# SCH.net
KiCad netlist of a schematic drawn in EasyEDA Pro
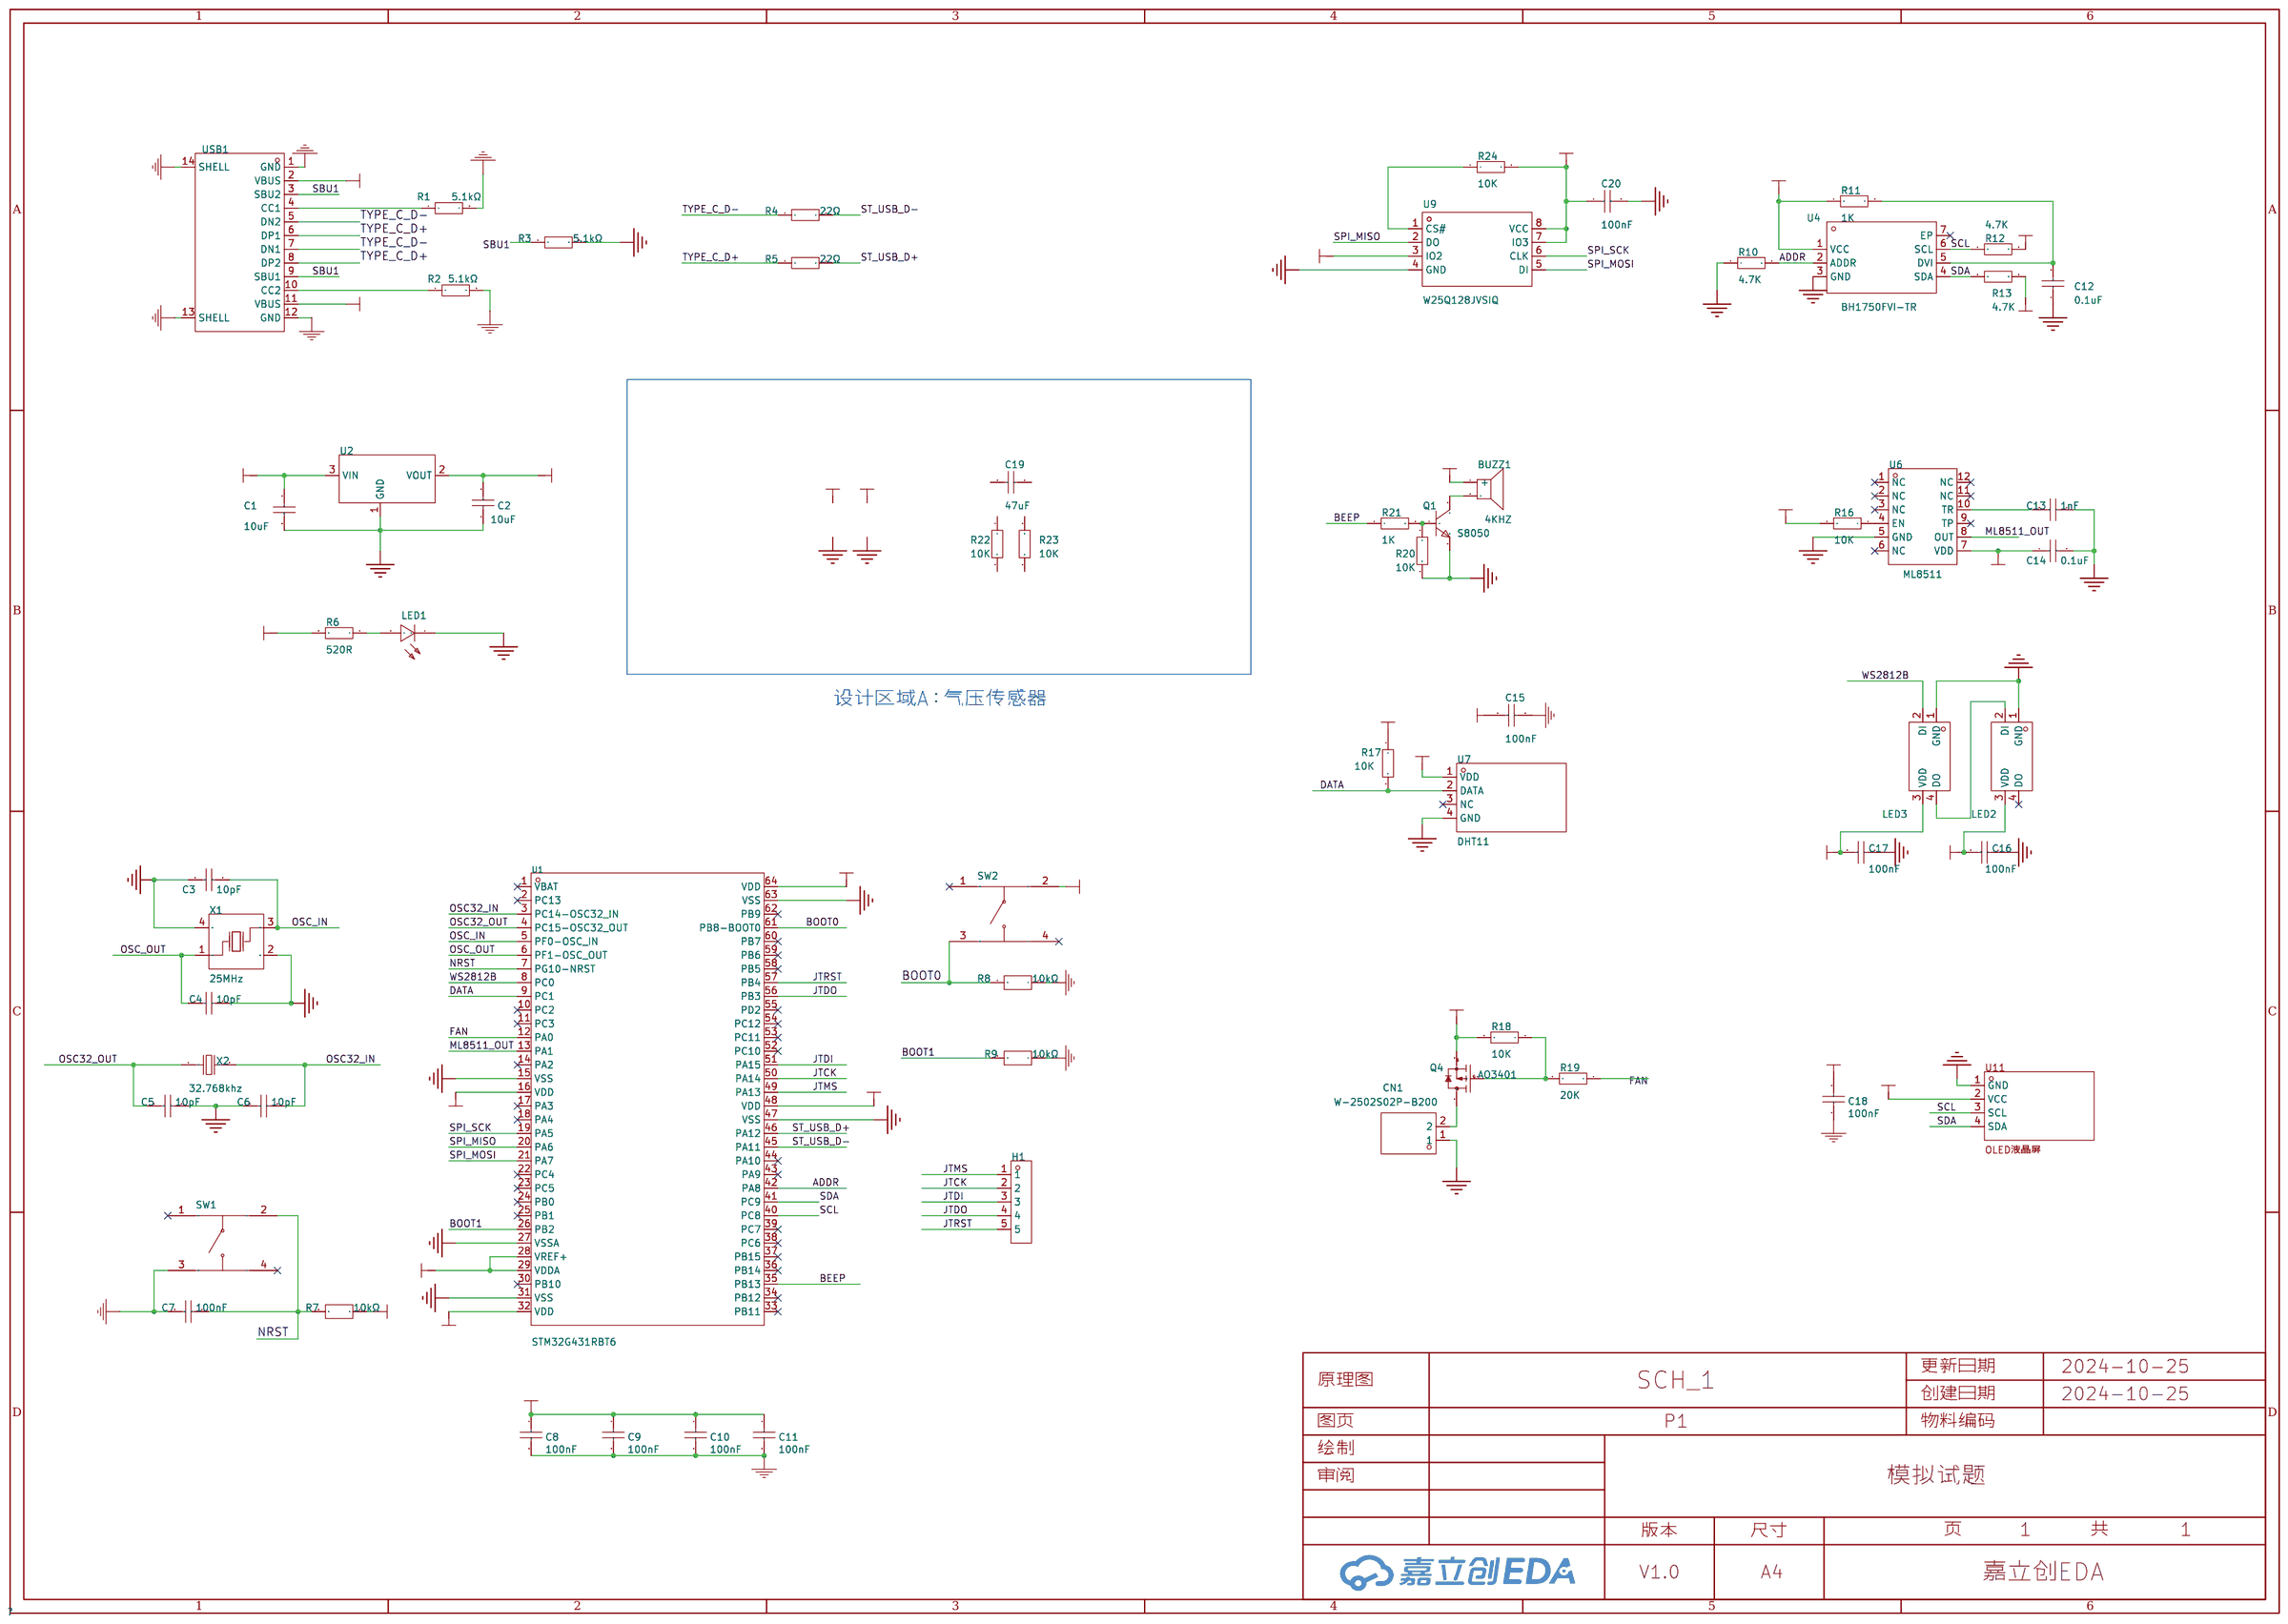
[diagram p0: schematic sheet]

(export (version "E")
  (design (tool "Eeschema 10.0.6"))
  (components
    (comp (ref "BUZZ1")
      (value "4KHZ")
      (footprint "easyedapro:BUZ-TH_BD12.0-P7.60-D0.6-FD")
      (description "驱动方式:有源(内含驱动线路);构造类型:电磁式;频率:2.7kHz;声压(SPL):85dB;")
      (fields (field (name "Manufacturer Part") "TMB12A05") (field (name "Manufacturer") "华能"))
      (libsource (lib "easyedapro") (part "TMB12A05"))
    )
    (comp (ref "C1")
      (value "10uF")
      (footprint "easyedapro:C0805")
      (description "容值:100nF;精度:±10%;额定电压:50V;材质(温度系数):X7R;")
      (fields
        (field (name "Manufacturer Part") "CC0805KRX7R9BB104")
        (field (name "Manufacturer") "YAGEO(国巨)")
      )
      (libsource (lib "easyedapro") (part "CC0805KRX7R9BB104"))
    )
    (comp (ref "C2")
      (value "10uF")
      (footprint "easyedapro:C0805")
      (description "容值:100nF;精度:±10%;额定电压:50V;材质(温度系数):X7R;")
      (fields
        (field (name "Manufacturer Part") "CC0805KRX7R9BB104")
        (field (name "Manufacturer") "YAGEO(国巨)")
      )
      (libsource (lib "easyedapro") (part "CC0805KRX7R9BB104"))
    )
    (comp (ref "C3")
      (value "10pF")
      (footprint "easyedapro:C0805")
      (description "容值:100nF;精度:±10%;额定电压:50V;材质(温度系数):X7R;")
      (fields
        (field (name "Manufacturer Part") "CC0805KRX7R9BB104")
        (field (name "Manufacturer") "YAGEO(国巨)")
      )
      (libsource (lib "easyedapro") (part "CC0805KRX7R9BB104"))
    )
    (comp (ref "C4")
      (value "10pF")
      (footprint "easyedapro:C0805")
      (description "容值:100nF;精度:±10%;额定电压:50V;材质(温度系数):X7R;")
      (fields
        (field (name "Manufacturer Part") "CC0805KRX7R9BB104")
        (field (name "Manufacturer") "YAGEO(国巨)")
      )
      (libsource (lib "easyedapro") (part "CC0805KRX7R9BB104"))
    )
    (comp (ref "C5")
      (value "10pF")
      (footprint "easyedapro:C0805")
      (description "容值:100nF;精度:±10%;额定电压:50V;材质(温度系数):X7R;")
      (fields
        (field (name "Manufacturer Part") "CC0805KRX7R9BB104")
        (field (name "Manufacturer") "YAGEO(国巨)")
      )
      (libsource (lib "easyedapro") (part "CC0805KRX7R9BB104"))
    )
    (comp (ref "C6")
      (value "10pF")
      (footprint "easyedapro:C0805")
      (description "容值:100nF;精度:±10%;额定电压:50V;材质(温度系数):X7R;")
      (fields
        (field (name "Manufacturer Part") "CC0805KRX7R9BB104")
        (field (name "Manufacturer") "YAGEO(国巨)")
      )
      (libsource (lib "easyedapro") (part "CC0805KRX7R9BB104"))
    )
    (comp (ref "C7") (value "100nF") (libsource (lib "easyedapro") (part "100nf")))
    (comp (ref "C8") (value "100nF") (libsource (lib "easyedapro") (part "100nf")))
    (comp (ref "C9") (value "100nF") (libsource (lib "easyedapro") (part "100nf")))
    (comp (ref "C10") (value "100nF") (libsource (lib "easyedapro") (part "100nf")))
    (comp (ref "C11") (value "100nF") (libsource (lib "easyedapro") (part "100nf")))
    (comp (ref "C12")
      (value "0.1uF")
      (footprint "easyedapro:C0805")
      (description "容值:100nF;精度:±10%;额定电压:50V;材质(温度系数):X7R;")
      (fields
        (field (name "Manufacturer Part") "CC0805KRX7R9BB104")
        (field (name "Manufacturer") "YAGEO(国巨)")
      )
      (libsource (lib "easyedapro") (part "CC0805KRX7R9BB104"))
    )
    (comp (ref "C13")
      (value "1nF")
      (footprint "easyedapro:C0805")
      (description "容值:100nF;精度:±10%;额定电压:50V;材质(温度系数):X7R;")
      (fields
        (field (name "Manufacturer Part") "CC0805KRX7R9BB104")
        (field (name "Manufacturer") "YAGEO(国巨)")
      )
      (libsource (lib "easyedapro") (part "CC0805KRX7R9BB104"))
    )
    (comp (ref "C14")
      (value "0.1uF")
      (footprint "easyedapro:C0805")
      (description "容值:100nF;精度:±10%;额定电压:50V;材质(温度系数):X7R;")
      (fields
        (field (name "Manufacturer Part") "CC0805KRX7R9BB104")
        (field (name "Manufacturer") "YAGEO(国巨)")
      )
      (libsource (lib "easyedapro") (part "CC0805KRX7R9BB104"))
    )
    (comp (ref "C15") (value "100nF") (libsource (lib "easyedapro") (part "100nf")))
    (comp (ref "C16")
      (value "100nF")
      (footprint "easyedapro:C0805")
      (description "容值:100nF;精度:±10%;额定电压:50V;材质(温度系数):X7R;")
      (fields
        (field (name "Manufacturer Part") "CC0805KRX7R9BB104")
        (field (name "Manufacturer") "YAGEO(国巨)")
      )
      (libsource (lib "easyedapro") (part "CC0805KRX7R9BB104"))
    )
    (comp (ref "C17")
      (value "100nF")
      (footprint "easyedapro:C0805")
      (description "容值:100nF;精度:±10%;额定电压:50V;材质(温度系数):X7R;")
      (fields
        (field (name "Manufacturer Part") "CC0805KRX7R9BB104")
        (field (name "Manufacturer") "YAGEO(国巨)")
      )
      (libsource (lib "easyedapro") (part "CC0805KRX7R9BB104"))
    )
    (comp (ref "C18") (value "100nF") (libsource (lib "easyedapro") (part "100nf")))
    (comp (ref "C19")
      (value "47uF")
      (footprint "easyedapro:C0805")
      (description "容值:100nF;精度:±10%;额定电压:50V;材质(温度系数):X7R;")
      (fields
        (field (name "Manufacturer Part") "CC0805KRX7R9BB104")
        (field (name "Manufacturer") "YAGEO(国巨)")
      )
      (libsource (lib "easyedapro") (part "CC0805KRX7R9BB104"))
    )
    (comp (ref "C20") (value "100nF") (libsource (lib "easyedapro") (part "100nf")))
    (comp (ref "CN1")
      (value "W-2502S02P-B200")
      (footprint "easyedapro:CONN-TH_2P-P2.54_2501S-2P")
      (description "插针结构:1x2P;间距:2.5mm;安装方式:-;参考系列:XH;总PIN数:2P;排数:1;每排PIN数:2;行距:-;触头材质:黄铜;")
      (fields (field (name "Manufacturer") "Ckmtw(灿科盟)"))
      (libsource (lib "easyedapro") (part "5V直流风扇"))
    )
    (comp (ref "H1")
      (value "~")
      (footprint "easyedapro:5P排针")
      (fields (field (name "Manufacturer Part") "68000-102HLF") (field (name "Manufacturer") "Amphenol ICC"))
      (libsource (lib "easyedapro") (part "5P排针"))
    )
    (comp (ref "LED1")
      (value "NCD0603R1")
      (footprint "easyedapro:LED0603-RD_RED")
      (fields (field (name "Manufacturer") "国星光电"))
      (libsource (lib "easyedapro") (part "FC-DA1608HRK-620D"))
    )
    (comp (ref "LED2")
      (value "XL-5050RGBC-WS2812B")
      (fields (field (name "Manufacturer") "XINGLIGHT(成兴光)"))
      (libsource (lib "easyedapro") (part "XL-3528RGBW-WS2812B"))
    )
    (comp (ref "LED3")
      (value "XL-5050RGBC-WS2812B")
      (fields (field (name "Manufacturer") "XINGLIGHT(成兴光)"))
      (libsource (lib "easyedapro") (part "XL-3528RGBW-WS2812B"))
    )
    (comp (ref "Q1")
      (value "S8050")
      (fields (field (name "Manufacturer") "宏迦橙"))
      (libsource (lib "easyedapro") (part "NPN"))
    )
    (comp (ref "Q4")
      (value "AO3401")
      (footprint "easyedapro:SOT-23-3_L2.9-W1.3-P1.90-LS2.4-BR")
      (fields (field (name "Manufacturer") "Hottech(合科泰)"))
      (libsource (lib "easyedapro") (part "AO3401"))
    )
    (comp (ref "R1") (value "5.1kΩ") (libsource (lib "easyedapro") (part "5.1kΩ")))
    (comp (ref "R2") (value "5.1kΩ") (libsource (lib "easyedapro") (part "5.1kΩ")))
    (comp (ref "R3") (value "5.1kΩ") (libsource (lib "easyedapro") (part "5.1kΩ")))
    (comp (ref "R4")
      (value "22Ω")
      (fields
        (field (name "Manufacturer Part") "0603WAF220JT5E")
        (field (name "Manufacturer") "UNI-ROYAL(厚声)")
      )
      (libsource (lib "easyedapro") (part "电阻"))
    )
    (comp (ref "R5")
      (value "22Ω")
      (fields
        (field (name "Manufacturer Part") "0603WAF220JT5E")
        (field (name "Manufacturer") "UNI-ROYAL(厚声)")
      )
      (libsource (lib "easyedapro") (part "电阻"))
    )
    (comp (ref "R6")
      (value "520R")
      (fields (field (name "Manufacturer Part") "RC0402FR-0710KL") (field (name "Manufacturer") "YAGEO(国巨)"))
      (libsource (lib "easyedapro") (part "电阻"))
    )
    (comp (ref "R7")
      (value "10kΩ")
      (fields (field (name "Manufacturer") "UNI-ROYAL(厚声)"))
      (libsource (lib "easyedapro") (part "10k"))
    )
    (comp (ref "R8")
      (value "10kΩ")
      (fields (field (name "Manufacturer") "UNI-ROYAL(厚声)"))
      (libsource (lib "easyedapro") (part "10k"))
    )
    (comp (ref "R9")
      (value "10kΩ")
      (fields (field (name "Manufacturer") "UNI-ROYAL(厚声)"))
      (libsource (lib "easyedapro") (part "10k"))
    )
    (comp (ref "R10")
      (value "4.7K")
      (footprint "easyedapro:R0603")
      (libsource (lib "easyedapro") (part "电阻"))
    )
    (comp (ref "R11") (value "1K") (footprint "easyedapro:R0603") (libsource (lib "easyedapro") (part "电阻")))
    (comp (ref "R12")
      (value "4.7K")
      (footprint "easyedapro:R0603")
      (libsource (lib "easyedapro") (part "电阻"))
    )
    (comp (ref "R13")
      (value "4.7K")
      (footprint "easyedapro:R0603")
      (libsource (lib "easyedapro") (part "电阻"))
    )
    (comp (ref "R16")
      (value "10K")
      (fields (field (name "Manufacturer Part") "RC0402FR-0710KL") (field (name "Manufacturer") "YAGEO(国巨)"))
      (libsource (lib "easyedapro") (part "电阻"))
    )
    (comp (ref "R17") (value "10K") (footprint "easyedapro:R0603") (libsource (lib "easyedapro") (part "电阻")))
    (comp (ref "R18") (value "10K") (footprint "easyedapro:R0603") (libsource (lib "easyedapro") (part "电阻")))
    (comp (ref "R19") (value "20K") (footprint "easyedapro:R0603") (libsource (lib "easyedapro") (part "电阻")))
    (comp (ref "R20") (value "10K") (footprint "easyedapro:R0603") (libsource (lib "easyedapro") (part "电阻")))
    (comp (ref "R21") (value "1K") (footprint "easyedapro:R0603") (libsource (lib "easyedapro") (part "电阻")))
    (comp (ref "R22") (value "10K") (footprint "easyedapro:R0603") (libsource (lib "easyedapro") (part "电阻")))
    (comp (ref "R23") (value "10K") (footprint "easyedapro:R0603") (libsource (lib "easyedapro") (part "电阻")))
    (comp (ref "R24") (value "10K") (footprint "easyedapro:R0603") (libsource (lib "easyedapro") (part "电阻")))
    (comp (ref "SW1")
      (value "TSA017A2540A07")
      (footprint "easyedapro:SW-SMD_4P-L4.2-W3.4-P2.15-LS5.2")
      (fields (field (name "Manufacturer") "BZCN(博众电气)"))
      (libsource (lib "easyedapro") (part "TSA017A2540A07"))
    )
    (comp (ref "SW2")
      (value "TSA017A2540A07")
      (footprint "easyedapro:SW-SMD_4P-L4.2-W3.4-P2.15-LS5.2")
      (fields (field (name "Manufacturer") "BZCN(博众电气)"))
      (libsource (lib "easyedapro") (part "TSA017A2540A07"))
    )
    (comp (ref "U1")
      (value "STM32G431RBT6")
      (footprint "easyedapro:LQFP-64_L10.0-W10.0-P0.50-LS12.0-BL")
      (description "CPU内核:ARM-M系列;程序存储容量:128KB;GPIO端口数量:52;工作电压范围:1.71V~3.6V;CPU最大主频:170MHz;")
      (fields (field (name "Manufacturer") "ST(意法半导体)"))
      (libsource (lib "easyedapro") (part "STM32G431RBT6"))
    )
    (comp (ref "U2")
      (value "AMS1117-3.3(XBLW)")
      (footprint "easyedapro:SOT-223-3_L6.5-W3.4-P2.30-LS7.0-BR-1")
      (description "最大输入电压:15V;输出电压:3.3V;最大输出电流:1A;电源纹波抑制比(PSRR):60dB;")
      (fields (field (name "Manufacturer") "XBLW(芯伯乐)"))
      (libsource (lib "easyedapro") (part "AMS1117-3.3(XBLW)_C18906017"))
    )
    (comp (ref "U4")
      (value "BH1750FVI-TR")
      (footprint "easyedapro:WSOF-6_L2.6-W1.6-P0.50-TL-EP")
      (description "检测颜色:-;接口类型:I2C;分辨率(位):16;")
      (fields (field (name "Manufacturer") "ROHM(罗姆)"))
      (libsource (lib "easyedapro") (part "BH1750FVI-TR"))
    )
    (comp (ref "U6")
      (value "ML8511")
      (footprint "easyedapro:DFN-12_L4.0-W3.7-P1.00-TL")
      (fields (field (name "Manufacturer") "ROHM(罗姆)"))
      (libsource (lib "easyedapro") (part "ML8511_REFBOARD"))
    )
    (comp (ref "U7")
      (value "DHT11")
      (footprint "easyedapro:SENSOR-TH_DHT11")
      (description "新款电容式数字温湿度传感器,老款已停产16.1x12.6x5.8mm")
      (fields (field (name "Manufacturer") "广州奥松"))
      (libsource (lib "easyedapro") (part "DHT11"))
    )
    (comp (ref "U8")
      (value "~")
      (footprint "easyedapro:CONN-TH_4P-P2.54_POGO-4P")
      (description "OLED液晶屏")
      (libsource (lib "easyedapro") (part "OLED液晶屏"))
    )
    (comp (ref "U9")
      (value "W25Q128JVSIQ")
      (footprint "easyedapro:SOIC-8_L5.3-W5.3-P1.27-LS8.0-BL")
      (description "存储器构架(格式):FLASH;存储器接口类型:SPI - Dual/Quad I/O;存储器容量:128Mb (16M x 8);")
      (fields (field (name "Manufacturer") "WINBOND(华邦)"))
      (libsource (lib "easyedapro") (part "W25Q128JVSIQTR"))
    )
    (comp (ref "USB1") (value "TYPE-C 16PIN 2MD(073)") (libsource (lib "easyedapro") (part "type-c 16pin")))
    (comp (ref "X1")
      (value "25MHz")
      (footprint "easyedapro:OSC-SMD_4P-L3.2-W2.5-BL")
      (description "晶振类型:贴片晶振;频率:25MHz;常温频差:±10ppm;外接负载电容:12pF;频率稳定度(全温):±20ppm;")
      (fields (field (name "Manufacturer Part") "X322525MOB4SI") (field (name "Manufacturer") "YXC(扬兴晶振)"))
      (libsource (lib "easyedapro") (part "X322525MOB4SI"))
    )
    (comp (ref "X2")
      (value "32.768kHz")
      (footprint "easyedapro:FC-135R_L3.2-W1.5")
      (description "频率:32.768kHz;晶振类型:贴片无源晶振;负载电容:12.5pF;等效串联电阻(ESR):70kΩ;频率公差:±20ppm;频率稳定度:-;工作温度:-40°C~+85°C;")
      (fields (field (name "Manufacturer Part") "Q13FC1350000400") (field (name "Manufacturer") "EPSON(爱普生)"))
      (libsource (lib "easyedapro") (part "Q13FC1350000400"))
    )
  )
  (nets
    (net (code "1") (name "/ADDR") (class "Default")
      (node (ref "R10") (pin "2") (pinfunction "2_2") (pintype "input"))
      (node (ref "U1") (pin "42") (pinfunction "PA8_42") (pintype "input"))
      (node (ref "U4") (pin "2") (pinfunction "ADDR_2") (pintype "unspecified"))
    )
    (net (code "2") (name "/BEEP") (class "Default")
      (node (ref "R21") (pin "1") (pinfunction "1_1") (pintype "input"))
      (node (ref "U1") (pin "35") (pinfunction "PB13_35") (pintype "input"))
    )
    (net (code "3") (name "/BOOT0") (class "Default")
      (node (ref "R8") (pin "2") (pinfunction "2_2") (pintype "unspecified"))
      (node (ref "SW2") (pin "3") (pinfunction "3_3") (pintype "unspecified"))
      (node (ref "U1") (pin "61") (pinfunction "PB8-BOOT0_61") (pintype "input"))
    )
    (net (code "4") (name "/BOOT1") (class "Default")
      (node (ref "R9") (pin "2") (pinfunction "2_2") (pintype "unspecified"))
      (node (ref "U1") (pin "26") (pinfunction "PB2_26") (pintype "input"))
    )
    (net (code "5") (name "/DATA") (class "Default")
      (node (ref "R17") (pin "2") (pinfunction "2_2") (pintype "input"))
      (node (ref "U1") (pin "9") (pinfunction "PC1_9") (pintype "input"))
      (node (ref "U7") (pin "2") (pinfunction "DATA_2") (pintype "unspecified"))
    )
    (net (code "6") (name "/FAN") (class "Default")
      (node (ref "R19") (pin "1") (pinfunction "1_1") (pintype "input"))
      (node (ref "U1") (pin "12") (pinfunction "PA0_12") (pintype "input"))
    )
    (net (code "7") (name "/JTCK") (class "Default")
      (node (ref "H1") (pin "2") (pinfunction "2_2") (pintype "input"))
      (node (ref "U1") (pin "50") (pinfunction "PA14_50") (pintype "input"))
    )
    (net (code "8") (name "/JTDI") (class "Default")
      (node (ref "H1") (pin "3") (pinfunction "3_3") (pintype "input"))
      (node (ref "U1") (pin "51") (pinfunction "PA15_51") (pintype "input"))
    )
    (net (code "9") (name "/JTDO") (class "Default")
      (node (ref "H1") (pin "4") (pinfunction "4_4") (pintype "input"))
      (node (ref "U1") (pin "56") (pinfunction "PB3_56") (pintype "input"))
    )
    (net (code "10") (name "/JTMS") (class "Default")
      (node (ref "H1") (pin "1") (pinfunction "1_1") (pintype "input"))
      (node (ref "U1") (pin "49") (pinfunction "PA13_49") (pintype "input"))
    )
    (net (code "11") (name "/JTRST") (class "Default")
      (node (ref "H1") (pin "5") (pinfunction "5_5") (pintype "input"))
      (node (ref "U1") (pin "57") (pinfunction "PB4_57") (pintype "input"))
    )
    (net (code "12") (name "/ML8511_OUT") (class "Default")
      (node (ref "U1") (pin "13") (pinfunction "PA1_13") (pintype "input"))
      (node (ref "U6") (pin "8") (pinfunction "OUT_8") (pintype "unspecified"))
    )
    (net (code "13") (name "/NRST") (class "Default")
      (node (ref "C7") (pin "1") (pinfunction "1_1") (pintype "input"))
      (node (ref "R7") (pin "2") (pinfunction "2_2") (pintype "unspecified"))
      (node (ref "SW1") (pin "2") (pinfunction "2_2") (pintype "unspecified"))
      (node (ref "U1") (pin "7") (pinfunction "PG10-NRST_7") (pintype "input"))
    )
    (net (code "14") (name "/OSC32_IN") (class "Default")
      (node (ref "C6") (pin "1") (pinfunction "1_1") (pintype "input"))
      (node (ref "U1") (pin "3") (pinfunction "PC14-OSC32_IN_3") (pintype "input"))
      (node (ref "X2") (pin "2") (pinfunction "2_2") (pintype "input"))
    )
    (net (code "15") (name "/OSC32_OUT") (class "Default")
      (node (ref "C5") (pin "2") (pinfunction "2_2") (pintype "input"))
      (node (ref "U1") (pin "4") (pinfunction "PC15-OSC32_OUT_4") (pintype "input"))
      (node (ref "X2") (pin "1") (pinfunction "1_1") (pintype "input"))
    )
    (net (code "16") (name "/OSC_IN") (class "Default")
      (node (ref "C3") (pin "2") (pinfunction "2_2") (pintype "input"))
      (node (ref "U1") (pin "5") (pinfunction "PF0-OSC_IN_5") (pintype "input"))
      (node (ref "X1") (pin "3") (pinfunction "OSC2_3") (pintype "unspecified"))
    )
    (net (code "17") (name "/OSC_OUT") (class "Default")
      (node (ref "C4") (pin "2") (pinfunction "2_2") (pintype "input"))
      (node (ref "U1") (pin "6") (pinfunction "PF1-OSC_OUT_6") (pintype "input"))
      (node (ref "X1") (pin "1") (pinfunction "OSC1_1") (pintype "unspecified"))
    )
    (net (code "18") (name "/SBU1") (class "Default")
      (node (ref "R3") (pin "1") (pinfunction "1_1") (pintype "input"))
      (node (ref "USB1") (pin "3") (pinfunction "SBU2_3") (pintype "unspecified"))
      (node (ref "USB1") (pin "9") (pinfunction "SBU1_9") (pintype "unspecified"))
    )
    (net (code "19") (name "/SCL") (class "Default")
      (node (ref "R12") (pin "1") (pinfunction "1_1") (pintype "input"))
      (node (ref "U1") (pin "40") (pinfunction "PC8_40") (pintype "input"))
      (node (ref "U4") (pin "6") (pinfunction "SCL_6") (pintype "unspecified"))
      (node (ref "U8") (pin "3") (pinfunction "SCL_3") (pintype "unspecified"))
    )
    (net (code "20") (name "/SDA") (class "Default")
      (node (ref "R13") (pin "1") (pinfunction "1_1") (pintype "input"))
      (node (ref "U1") (pin "41") (pinfunction "PC9_41") (pintype "input"))
      (node (ref "U4") (pin "4") (pinfunction "SDA_4") (pintype "unspecified"))
      (node (ref "U8") (pin "4") (pinfunction "SDA_4") (pintype "unspecified"))
    )
    (net (code "21") (name "/SPI_MISO") (class "Default")
      (node (ref "U1") (pin "20") (pinfunction "PA6_20") (pintype "input"))
      (node (ref "U9") (pin "2") (pinfunction "DO_2") (pintype "input"))
    )
    (net (code "22") (name "/SPI_MOSI") (class "Default")
      (node (ref "U1") (pin "21") (pinfunction "PA7_21") (pintype "input"))
      (node (ref "U9") (pin "5") (pinfunction "DI_5") (pintype "input"))
    )
    (net (code "23") (name "/SPI_SCK") (class "Default")
      (node (ref "U1") (pin "19") (pinfunction "PA5_19") (pintype "input"))
      (node (ref "U9") (pin "6") (pinfunction "CLK_6") (pintype "input"))
    )
    (net (code "24") (name "/ST_USB_D+") (class "Default")
      (node (ref "R5") (pin "2") (pinfunction "2_2") (pintype "input"))
      (node (ref "U1") (pin "46") (pinfunction "PA12_46") (pintype "input"))
    )
    (net (code "25") (name "/ST_USB_D-") (class "Default")
      (node (ref "R4") (pin "2") (pinfunction "2_2") (pintype "input"))
      (node (ref "U1") (pin "45") (pinfunction "PA11_45") (pintype "input"))
    )
    (net (code "26") (name "/TYPE_C_D+") (class "Default")
      (node (ref "R5") (pin "1") (pinfunction "1_1") (pintype "input"))
      (node (ref "USB1") (pin "6") (pinfunction "DP1_6") (pintype "unspecified"))
      (node (ref "USB1") (pin "8") (pinfunction "DP2_8") (pintype "unspecified"))
    )
    (net (code "27") (name "/TYPE_C_D-") (class "Default")
      (node (ref "R4") (pin "1") (pinfunction "1_1") (pintype "input"))
      (node (ref "USB1") (pin "5") (pinfunction "DN2_5") (pintype "unspecified"))
      (node (ref "USB1") (pin "7") (pinfunction "DN1_7") (pintype "unspecified"))
    )
    (net (code "28") (name "/WS2812B") (class "Default")
      (node (ref "LED3") (pin "2") (pinfunction "DI_2") (pintype "input"))
      (node (ref "U1") (pin "8") (pinfunction "PC0_8") (pintype "input"))
    )
    (net (code "29") (name "3.3V") (class "Default")
      (node (ref "BUZZ1") (pin "1") (pinfunction "+_1") (pintype "unspecified"))
      (node (ref "C10") (pin "1") (pinfunction "1_1") (pintype "input"))
      (node (ref "C11") (pin "1") (pinfunction "1_1") (pintype "input"))
      (node (ref "C14") (pin "1") (pinfunction "1_1") (pintype "input"))
      (node (ref "C15") (pin "1") (pinfunction "1_1") (pintype "input"))
      (node (ref "C18") (pin "1") (pinfunction "1_1") (pintype "input"))
      (node (ref "C2") (pin "2") (pinfunction "2_2") (pintype "input"))
      (node (ref "C20") (pin "1") (pinfunction "1_1") (pintype "input"))
      (node (ref "C8") (pin "1") (pinfunction "1_1") (pintype "input"))
      (node (ref "C9") (pin "1") (pinfunction "1_1") (pintype "input"))
      (node (ref "R11") (pin "1") (pinfunction "1_1") (pintype "input"))
      (node (ref "R12") (pin "2") (pinfunction "2_2") (pintype "input"))
      (node (ref "R13") (pin "2") (pinfunction "2_2") (pintype "input"))
      (node (ref "R16") (pin "2") (pinfunction "2_2") (pintype "input"))
      (node (ref "R17") (pin "1") (pinfunction "1_1") (pintype "input"))
      (node (ref "R24") (pin "2") (pinfunction "2_2") (pintype "input"))
      (node (ref "R6") (pin "2") (pinfunction "2_2") (pintype "input"))
      (node (ref "R7") (pin "1") (pinfunction "1_1") (pintype "unspecified"))
      (node (ref "SW2") (pin "2") (pinfunction "2_2") (pintype "unspecified"))
      (node (ref "U1") (pin "16") (pinfunction "VDD_16") (pintype "input"))
      (node (ref "U1") (pin "28") (pinfunction "VREF+_28") (pintype "input"))
      (node (ref "U1") (pin "29") (pinfunction "VDDA_29") (pintype "input"))
      (node (ref "U1") (pin "32") (pinfunction "VDD_32") (pintype "input"))
      (node (ref "U1") (pin "48") (pinfunction "VDD_48") (pintype "input"))
      (node (ref "U1") (pin "64") (pinfunction "VDD_64") (pintype "input"))
      (node (ref "U2") (pin "2") (pinfunction "VOUT_2") (pintype "unspecified"))
      (node (ref "U4") (pin "1") (pinfunction "VCC_1") (pintype "unspecified"))
      (node (ref "U6") (pin "7") (pinfunction "VDD_7") (pintype "unspecified"))
      (node (ref "U7") (pin "1") (pinfunction "VDD_1") (pintype "unspecified"))
      (node (ref "U8") (pin "2") (pinfunction "VCC_2") (pintype "unspecified"))
      (node (ref "U9") (pin "3") (pinfunction "IO2_3") (pintype "input"))
      (node (ref "U9") (pin "7") (pinfunction "IO3_7") (pintype "input"))
      (node (ref "U9") (pin "8") (pinfunction "VCC_8") (pintype "input"))
    )
    (net (code "30") (name "5V") (class "Default")
      (node (ref "C1") (pin "1") (pinfunction "1_1") (pintype "input"))
      (node (ref "C16") (pin "2") (pinfunction "2_2") (pintype "input"))
      (node (ref "C17") (pin "2") (pinfunction "2_2") (pintype "input"))
      (node (ref "LED2") (pin "3") (pinfunction "VDD_3") (pintype "input"))
      (node (ref "LED3") (pin "3") (pinfunction "VDD_3") (pintype "input"))
      (node (ref "Q4") (pin "2") (pinfunction "S_2") (pintype "unspecified"))
      (node (ref "R18") (pin "2") (pinfunction "2_2") (pintype "input"))
      (node (ref "U2") (pin "3") (pinfunction "VIN_3") (pintype "unspecified"))
      (node (ref "USB1") (pin "11") (pinfunction "VBUS_11") (pintype "unspecified"))
      (node (ref "USB1") (pin "2") (pinfunction "VBUS_2") (pintype "unspecified"))
    )
    (net (code "31") (name "GND") (class "Default")
      (node (ref "C1") (pin "2") (pinfunction "2_2") (pintype "input"))
      (node (ref "C10") (pin "2") (pinfunction "2_2") (pintype "input"))
      (node (ref "C11") (pin "2") (pinfunction "2_2") (pintype "input"))
      (node (ref "C12") (pin "1") (pinfunction "1_1") (pintype "input"))
      (node (ref "C13") (pin "1") (pinfunction "1_1") (pintype "input"))
      (node (ref "C14") (pin "2") (pinfunction "2_2") (pintype "input"))
      (node (ref "C15") (pin "2") (pinfunction "2_2") (pintype "input"))
      (node (ref "C16") (pin "1") (pinfunction "1_1") (pintype "input"))
      (node (ref "C17") (pin "1") (pinfunction "1_1") (pintype "input"))
      (node (ref "C18") (pin "2") (pinfunction "2_2") (pintype "input"))
      (node (ref "C2") (pin "1") (pinfunction "1_1") (pintype "input"))
      (node (ref "C20") (pin "2") (pinfunction "2_2") (pintype "input"))
      (node (ref "C3") (pin "1") (pinfunction "1_1") (pintype "input"))
      (node (ref "C4") (pin "1") (pinfunction "1_1") (pintype "input"))
      (node (ref "C5") (pin "1") (pinfunction "1_1") (pintype "input"))
      (node (ref "C6") (pin "2") (pinfunction "2_2") (pintype "input"))
      (node (ref "C7") (pin "2") (pinfunction "2_2") (pintype "input"))
      (node (ref "C8") (pin "2") (pinfunction "2_2") (pintype "input"))
      (node (ref "C9") (pin "2") (pinfunction "2_2") (pintype "input"))
      (node (ref "CN1") (pin "1") (pinfunction "1_1") (pintype "unspecified"))
      (node (ref "LED1") (pin "1") (pinfunction "K_1") (pintype "input"))
      (node (ref "LED2") (pin "1") (pinfunction "GND_1") (pintype "input"))
      (node (ref "LED3") (pin "1") (pinfunction "GND_1") (pintype "input"))
      (node (ref "Q1") (pin "2") (pinfunction "2_2") (pintype "unspecified"))
      (node (ref "R1") (pin "2") (pinfunction "2_2") (pintype "input"))
      (node (ref "R10") (pin "1") (pinfunction "1_1") (pintype "input"))
      (node (ref "R2") (pin "2") (pinfunction "2_2") (pintype "input"))
      (node (ref "R20") (pin "2") (pinfunction "2_2") (pintype "input"))
      (node (ref "R3") (pin "2") (pinfunction "2_2") (pintype "input"))
      (node (ref "R8") (pin "1") (pinfunction "1_1") (pintype "unspecified"))
      (node (ref "R9") (pin "1") (pinfunction "1_1") (pintype "unspecified"))
      (node (ref "SW1") (pin "3") (pinfunction "3_3") (pintype "unspecified"))
      (node (ref "U1") (pin "15") (pinfunction "VSS_15") (pintype "input"))
      (node (ref "U1") (pin "27") (pinfunction "VSSA_27") (pintype "input"))
      (node (ref "U1") (pin "31") (pinfunction "VSS_31") (pintype "input"))
      (node (ref "U1") (pin "47") (pinfunction "VSS_47") (pintype "input"))
      (node (ref "U1") (pin "63") (pinfunction "VSS_63") (pintype "input"))
      (node (ref "U2") (pin "1") (pinfunction "GND_1") (pintype "unspecified"))
      (node (ref "U4") (pin "3") (pinfunction "GND_3") (pintype "unspecified"))
      (node (ref "U6") (pin "5") (pinfunction "GND_5") (pintype "unspecified"))
      (node (ref "U7") (pin "4") (pinfunction "GND_4") (pintype "unspecified"))
      (node (ref "U8") (pin "1") (pinfunction "GND_1") (pintype "unspecified"))
      (node (ref "U9") (pin "4") (pinfunction "GND_4") (pintype "input"))
      (node (ref "USB1") (pin "1") (pinfunction "GND_1") (pintype "unspecified"))
      (node (ref "USB1") (pin "12") (pinfunction "GND_12") (pintype "unspecified"))
      (node (ref "USB1") (pin "13") (pinfunction "SHELL_13") (pintype "unspecified"))
      (node (ref "USB1") (pin "14") (pinfunction "SHELL_14") (pintype "unspecified"))
      (node (ref "X1") (pin "2") (pinfunction "GND_2") (pintype "unspecified"))
      (node (ref "X1") (pin "4") (pinfunction "GND_4") (pintype "unspecified"))
    )
    (net (code "32") (name "Net-(BUZZ1-Pad2)") (class "Default")
      (node (ref "BUZZ1") (pin "2") (pinfunction "2_2") (pintype "unspecified"))
      (node (ref "Q1") (pin "3") (pinfunction "3_3") (pintype "unspecified"))
    )
    (net (code "33") (name "Net-(LED1-A)") (class "Default")
      (node (ref "LED1") (pin "2") (pinfunction "A_2") (pintype "input"))
      (node (ref "R6") (pin "1") (pinfunction "1_1") (pintype "input"))
    )
    (net (code "34") (name "Net-(LED2-DI)") (class "Default")
      (node (ref "LED2") (pin "2") (pinfunction "DI_2") (pintype "input"))
      (node (ref "LED3") (pin "4") (pinfunction "DO_4") (pintype "input"))
    )
    (net (code "35") (name "Net-(Q1-Pad1)") (class "Default")
      (node (ref "Q1") (pin "1") (pinfunction "1_1") (pintype "unspecified"))
      (node (ref "R20") (pin "1") (pinfunction "1_1") (pintype "input"))
      (node (ref "R21") (pin "2") (pinfunction "2_2") (pintype "input"))
    )
    (net (code "36") (name "Net-(Q4-D)") (class "Default")
      (node (ref "CN1") (pin "2") (pinfunction "2_2") (pintype "unspecified"))
      (node (ref "Q4") (pin "3") (pinfunction "D_3") (pintype "unspecified"))
    )
    (net (code "37") (name "Net-(Q4-G)") (class "Default")
      (node (ref "Q4") (pin "1") (pinfunction "G_1") (pintype "unspecified"))
      (node (ref "R18") (pin "1") (pinfunction "1_1") (pintype "input"))
      (node (ref "R19") (pin "2") (pinfunction "2_2") (pintype "input"))
    )
    (net (code "38") (name "Net-(U4-DVI)") (class "Default")
      (node (ref "C12") (pin "2") (pinfunction "2_2") (pintype "input"))
      (node (ref "R11") (pin "2") (pinfunction "2_2") (pintype "input"))
      (node (ref "U4") (pin "5") (pinfunction "DVI_5") (pintype "unspecified"))
    )
    (net (code "39") (name "Net-(U6-EN)") (class "Default")
      (node (ref "R16") (pin "1") (pinfunction "1_1") (pintype "input"))
      (node (ref "U6") (pin "4") (pinfunction "EN_4") (pintype "unspecified"))
    )
    (net (code "40") (name "Net-(U6-TR)") (class "Default")
      (node (ref "C13") (pin "2") (pinfunction "2_2") (pintype "input"))
      (node (ref "U6") (pin "10") (pinfunction "TR_10") (pintype "unspecified"))
    )
    (net (code "41") (name "Net-(U9-CS#)") (class "Default")
      (node (ref "R24") (pin "1") (pinfunction "1_1") (pintype "input"))
      (node (ref "U9") (pin "1") (pinfunction "CS#_1") (pintype "input"))
    )
    (net (code "42") (name "Net-(USB1-CC1)") (class "Default")
      (node (ref "R1") (pin "1") (pinfunction "1_1") (pintype "input"))
      (node (ref "USB1") (pin "4") (pinfunction "CC1_4") (pintype "unspecified"))
    )
    (net (code "43") (name "Net-(USB1-CC2)") (class "Default")
      (node (ref "R2") (pin "1") (pinfunction "1_1") (pintype "input"))
      (node (ref "USB1") (pin "10") (pinfunction "CC2_10") (pintype "unspecified"))
    )
    (net (code "44") (name "unconnected-(C19-Pad1)") (class "Default")
      (node (ref "C19") (pin "1") (pinfunction "1_1") (pintype "input"))
    )
    (net (code "45") (name "unconnected-(C19-Pad2)") (class "Default")
      (node (ref "C19") (pin "2") (pinfunction "2_2") (pintype "input"))
    )
    (net (code "46") (name "unconnected-(LED2-DO-Pad4)") (class "Default")
      (node (ref "LED2") (pin "4") (pinfunction "DO_4") (pintype "input+no_connect"))
    )
    (net (code "47") (name "unconnected-(R22-Pad1)") (class "Default")
      (node (ref "R22") (pin "1") (pinfunction "1_1") (pintype "input"))
    )
    (net (code "48") (name "unconnected-(R22-Pad2)") (class "Default")
      (node (ref "R22") (pin "2") (pinfunction "2_2") (pintype "input"))
    )
    (net (code "49") (name "unconnected-(R23-Pad1)") (class "Default")
      (node (ref "R23") (pin "1") (pinfunction "1_1") (pintype "input"))
    )
    (net (code "50") (name "unconnected-(R23-Pad2)") (class "Default")
      (node (ref "R23") (pin "2") (pinfunction "2_2") (pintype "input"))
    )
    (net (code "51") (name "unconnected-(SW1-Pad1)") (class "Default")
      (node (ref "SW1") (pin "1") (pinfunction "1_1") (pintype "unspecified+no_connect"))
    )
    (net (code "52") (name "unconnected-(SW1-Pad4)") (class "Default")
      (node (ref "SW1") (pin "4") (pinfunction "4_4") (pintype "unspecified+no_connect"))
    )
    (net (code "53") (name "unconnected-(SW2-Pad1)") (class "Default")
      (node (ref "SW2") (pin "1") (pinfunction "1_1") (pintype "unspecified+no_connect"))
    )
    (net (code "54") (name "unconnected-(SW2-Pad4)") (class "Default")
      (node (ref "SW2") (pin "4") (pinfunction "4_4") (pintype "unspecified+no_connect"))
    )
    (net (code "55") (name "unconnected-(U1-PA2-Pad14)") (class "Default")
      (node (ref "U1") (pin "14") (pinfunction "PA2_14") (pintype "input+no_connect"))
    )
    (net (code "56") (name "unconnected-(U1-PA3-Pad17)") (class "Default")
      (node (ref "U1") (pin "17") (pinfunction "PA3_17") (pintype "input+no_connect"))
    )
    (net (code "57") (name "unconnected-(U1-PA4-Pad18)") (class "Default")
      (node (ref "U1") (pin "18") (pinfunction "PA4_18") (pintype "input+no_connect"))
    )
    (net (code "58") (name "unconnected-(U1-PA9-Pad43)") (class "Default")
      (node (ref "U1") (pin "43") (pinfunction "PA9_43") (pintype "input+no_connect"))
    )
    (net (code "59") (name "unconnected-(U1-PA10-Pad44)") (class "Default")
      (node (ref "U1") (pin "44") (pinfunction "PA10_44") (pintype "input+no_connect"))
    )
    (net (code "60") (name "unconnected-(U1-PB0-Pad24)") (class "Default")
      (node (ref "U1") (pin "24") (pinfunction "PB0_24") (pintype "input+no_connect"))
    )
    (net (code "61") (name "unconnected-(U1-PB1-Pad25)") (class "Default")
      (node (ref "U1") (pin "25") (pinfunction "PB1_25") (pintype "input+no_connect"))
    )
    (net (code "62") (name "unconnected-(U1-PB5-Pad58)") (class "Default")
      (node (ref "U1") (pin "58") (pinfunction "PB5_58") (pintype "input+no_connect"))
    )
    (net (code "63") (name "unconnected-(U1-PB6-Pad59)") (class "Default")
      (node (ref "U1") (pin "59") (pinfunction "PB6_59") (pintype "input+no_connect"))
    )
    (net (code "64") (name "unconnected-(U1-PB7-Pad60)") (class "Default")
      (node (ref "U1") (pin "60") (pinfunction "PB7_60") (pintype "input+no_connect"))
    )
    (net (code "65") (name "unconnected-(U1-PB9-Pad62)") (class "Default")
      (node (ref "U1") (pin "62") (pinfunction "PB9_62") (pintype "input+no_connect"))
    )
    (net (code "66") (name "unconnected-(U1-PB10-Pad30)") (class "Default")
      (node (ref "U1") (pin "30") (pinfunction "PB10_30") (pintype "input+no_connect"))
    )
    (net (code "67") (name "unconnected-(U1-PB11-Pad33)") (class "Default")
      (node (ref "U1") (pin "33") (pinfunction "PB11_33") (pintype "input+no_connect"))
    )
    (net (code "68") (name "unconnected-(U1-PB12-Pad34)") (class "Default")
      (node (ref "U1") (pin "34") (pinfunction "PB12_34") (pintype "input+no_connect"))
    )
    (net (code "69") (name "unconnected-(U1-PB14-Pad36)") (class "Default")
      (node (ref "U1") (pin "36") (pinfunction "PB14_36") (pintype "input+no_connect"))
    )
    (net (code "70") (name "unconnected-(U1-PB15-Pad37)") (class "Default")
      (node (ref "U1") (pin "37") (pinfunction "PB15_37") (pintype "input+no_connect"))
    )
    (net (code "71") (name "unconnected-(U1-PC2-Pad10)") (class "Default")
      (node (ref "U1") (pin "10") (pinfunction "PC2_10") (pintype "input+no_connect"))
    )
    (net (code "72") (name "unconnected-(U1-PC3-Pad11)") (class "Default")
      (node (ref "U1") (pin "11") (pinfunction "PC3_11") (pintype "input+no_connect"))
    )
    (net (code "73") (name "unconnected-(U1-PC4-Pad22)") (class "Default")
      (node (ref "U1") (pin "22") (pinfunction "PC4_22") (pintype "input+no_connect"))
    )
    (net (code "74") (name "unconnected-(U1-PC5-Pad23)") (class "Default")
      (node (ref "U1") (pin "23") (pinfunction "PC5_23") (pintype "input+no_connect"))
    )
    (net (code "75") (name "unconnected-(U1-PC6-Pad38)") (class "Default")
      (node (ref "U1") (pin "38") (pinfunction "PC6_38") (pintype "input+no_connect"))
    )
    (net (code "76") (name "unconnected-(U1-PC7-Pad39)") (class "Default")
      (node (ref "U1") (pin "39") (pinfunction "PC7_39") (pintype "input+no_connect"))
    )
    (net (code "77") (name "unconnected-(U1-PC10-Pad52)") (class "Default")
      (node (ref "U1") (pin "52") (pinfunction "PC10_52") (pintype "input+no_connect"))
    )
    (net (code "78") (name "unconnected-(U1-PC11-Pad53)") (class "Default")
      (node (ref "U1") (pin "53") (pinfunction "PC11_53") (pintype "input+no_connect"))
    )
    (net (code "79") (name "unconnected-(U1-PC12-Pad54)") (class "Default")
      (node (ref "U1") (pin "54") (pinfunction "PC12_54") (pintype "input+no_connect"))
    )
    (net (code "80") (name "unconnected-(U1-PC13-Pad2)") (class "Default")
      (node (ref "U1") (pin "2") (pinfunction "PC13_2") (pintype "input+no_connect"))
    )
    (net (code "81") (name "unconnected-(U1-PD2-Pad55)") (class "Default")
      (node (ref "U1") (pin "55") (pinfunction "PD2_55") (pintype "input+no_connect"))
    )
    (net (code "82") (name "unconnected-(U1-VBAT-Pad1)") (class "Default")
      (node (ref "U1") (pin "1") (pinfunction "VBAT_1") (pintype "input+no_connect"))
    )
    (net (code "83") (name "unconnected-(U4-EP-Pad7)") (class "Default")
      (node (ref "U4") (pin "7") (pinfunction "EP_7") (pintype "unspecified+no_connect"))
    )
    (net (code "84") (name "unconnected-(U6-NC-Pad1)") (class "Default")
      (node (ref "U6") (pin "1") (pinfunction "NC_1") (pintype "unspecified+no_connect"))
    )
    (net (code "85") (name "unconnected-(U6-NC-Pad2)") (class "Default")
      (node (ref "U6") (pin "2") (pinfunction "NC_2") (pintype "unspecified+no_connect"))
    )
    (net (code "86") (name "unconnected-(U6-NC-Pad3)") (class "Default")
      (node (ref "U6") (pin "3") (pinfunction "NC_3") (pintype "unspecified+no_connect"))
    )
    (net (code "87") (name "unconnected-(U6-NC-Pad6)") (class "Default")
      (node (ref "U6") (pin "6") (pinfunction "NC_6") (pintype "unspecified+no_connect"))
    )
    (net (code "88") (name "unconnected-(U6-NC-Pad11)") (class "Default")
      (node (ref "U6") (pin "11") (pinfunction "NC_11") (pintype "unspecified+no_connect"))
    )
    (net (code "89") (name "unconnected-(U6-NC-Pad12)") (class "Default")
      (node (ref "U6") (pin "12") (pinfunction "NC_12") (pintype "unspecified+no_connect"))
    )
    (net (code "90") (name "unconnected-(U6-TP-Pad9)") (class "Default")
      (node (ref "U6") (pin "9") (pinfunction "TP_9") (pintype "unspecified+no_connect"))
    )
    (net (code "91") (name "unconnected-(U7-NC-Pad3)") (class "Default")
      (node (ref "U7") (pin "3") (pinfunction "NC_3") (pintype "unspecified+no_connect"))
    )
  )
)
